# Module_RS485.net
KiCad netlist of a schematic drawn in Altium Designer
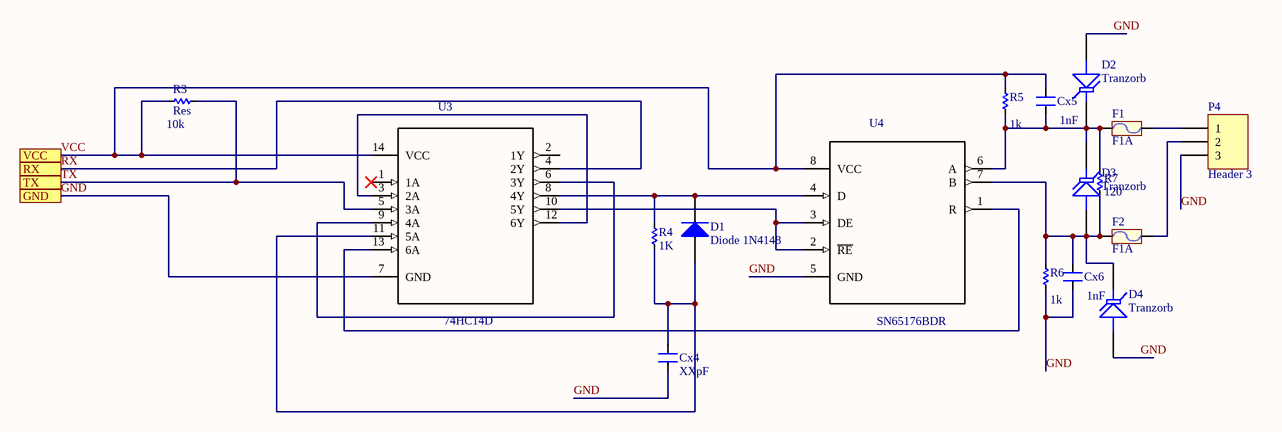
[diagram p0: Module RS485.SchDoc]

(export (version "E")
  (design (tool "Eeschema 10.0.6"))
  (components
    (comp (ref "Cx4")
      (value "XXpF")
      (footprint "CN-SMD-1206")
      (libsource (lib "LIBRARY_altium mulinhkien") (part "CN"))
    )
    (comp (ref "Cx5")
      (value "1nF")
      (footprint "CN-SMD-1206")
      (libsource (lib "LIBRARY_altium mulinhkien") (part "CN"))
    )
    (comp (ref "Cx6")
      (value "1nF")
      (footprint "CN-SMD-1206")
      (libsource (lib "LIBRARY_altium mulinhkien") (part "CN"))
    )
    (comp (ref "D1")
      (value "Diode 1N4148")
      (footprint "DO-35")
      (description "High Conductance Fast Diode")
      (fields (field (name "PUBLISHER") "Altium Limited"))
      (libsource (lib "Miscellaneous Devices") (part "Diode 1N4148"))
    )
    (comp (ref "D2")
      (value "Tranzorb")
      (footprint "DO-7")
      (description "Transient Voltage Suppression (TVS) Diode")
      (fields (field (name "PUBLISHER") "Altium Limited"))
      (libsource (lib "Miscellaneous Devices") (part "Tranzorb"))
    )
    (comp (ref "D3")
      (value "Tranzorb")
      (footprint "DO-7")
      (description "Transient Voltage Suppression (TVS) Diode")
      (fields (field (name "PUBLISHER") "Altium Limited"))
      (libsource (lib "Miscellaneous Devices") (part "Tranzorb"))
    )
    (comp (ref "D4")
      (value "Tranzorb")
      (footprint "DO-7")
      (description "Transient Voltage Suppression (TVS) Diode")
      (fields (field (name "PUBLISHER") "Altium Limited"))
      (libsource (lib "Miscellaneous Devices") (part "Tranzorb"))
    )
    (comp (ref "F1")
      (value "F1A")
      (footprint "Fuse3")
      (description "Fuse")
      (fields (field (name "DESIGNED BY") "VanDungEvn"))
      (libsource (lib "LIBRARY_altium mulinhkien") (part "Fuse"))
    )
    (comp (ref "F2")
      (value "F1A")
      (footprint "Fuse3")
      (description "Fuse")
      (fields (field (name "DESIGNED BY") "VanDungEvn"))
      (libsource (lib "LIBRARY_altium mulinhkien") (part "Fuse"))
    )
    (comp (ref "P4")
      (value "Header 3")
      (footprint "HDR1X3")
      (description "Header, 3-Pin")
      (fields (field (name "PUBLISHER") "Altium Limited"))
      (libsource (lib "Miscellaneous Connectors") (part "Header 3"))
    )
    (comp (ref "R3")
      (value "Res")
      (footprint "RES-SMD-1206")
      (description "Resistor")
      (fields
        (field (name "MANUFACTURER") "Generic Components")
        (field (name "ALTIUM_VALUE") "10k")
        (field (name "PUBLISHER") "Altium Hobart Technology Centre")
      )
      (libsource (lib "LIBRARY_altium mulinhkien") (part "Res-SMD"))
    )
    (comp (ref "R4")
      (value "1K")
      (footprint "RES-SMD-1206")
      (description "Resistor")
      (fields
        (field (name "MANUFACTURER") "Generic Components")
        (field (name "PUBLISHER") "Altium Hobart Technology Centre")
      )
      (libsource (lib "LIBRARY_altium mulinhkien") (part "Res-SMD"))
    )
    (comp (ref "R5")
      (value "1k")
      (footprint "RES-SMD-1206")
      (description "Resistor")
      (fields
        (field (name "MANUFACTURER") "Generic Components")
        (field (name "PUBLISHER") "Altium Hobart Technology Centre")
      )
      (libsource (lib "LIBRARY_altium mulinhkien") (part "Res-SMD"))
    )
    (comp (ref "R6")
      (value "1k")
      (footprint "RES-SMD-1206")
      (description "Resistor")
      (fields
        (field (name "MANUFACTURER") "Generic Components")
        (field (name "PUBLISHER") "Altium Hobart Technology Centre")
      )
      (libsource (lib "LIBRARY_altium mulinhkien") (part "Res-SMD"))
    )
    (comp (ref "R7")
      (value "120")
      (footprint "RES-SMD-1206")
      (description "Resistor")
      (fields
        (field (name "MANUFACTURER") "Generic Components")
        (field (name "PUBLISHER") "Altium Hobart Technology Centre")
      )
      (libsource (lib "LIBRARY_altium mulinhkien") (part "Res-SMD"))
    )
    (comp (ref "U3")
      (value "74HC14D")
      (footprint "*SOIC127P600X175-14N")
      (description "74HC CMOS logic IC series SOIC14 Hex Schmitt Inverter")
      (fields
        (field (name "DIGI-KEY_PART_NUMBER") "74HC14DCT-ND")
        (field (name "MF") "Toshiba Semiconductor")
      )
      (libsource (lib "74HC14D") (part "74HC14D"))
    )
    (comp (ref "U4")
      (value "SN65176BDR")
      (footprint "*SOIC127P600X175-8N")
      (description "Single Transmitter/Receiver RS-422/RS-485 8-Pin SOIC T/R")
      (fields (field (name "DIGI-KEY_PART_NUMBER") "296-14636-1-ND") (field (name "MF") "Texas Instruments"))
      (libsource (lib "SN65176BDR") (part "SN65176BDR"))
    )
  )
  (nets
    (net (code "1") (name "/GND") (class "Default")
      (node (ref "Cx4") (pin "1") (pinfunction "1_1") (pintype "passive"))
      (node (ref "Cx6") (pin "2") (pinfunction "2_2") (pintype "passive"))
      (node (ref "D2") (pin "1") (pinfunction "A_1") (pintype "passive"))
      (node (ref "D4") (pin "1") (pinfunction "A_1") (pintype "passive"))
      (node (ref "P4") (pin "3") (pinfunction "3_3") (pintype "passive"))
      (node (ref "R6") (pin "1") (pinfunction "1_1") (pintype "passive"))
      (node (ref "U3") (pin "7") (pinfunction "GND_7") (pintype "passive"))
      (node (ref "U4") (pin "5") (pinfunction "GND_5") (pintype "passive"))
    )
    (net (code "2") (name "/RX") (class "Default")
      (node (ref "U3") (pin "4") (pinfunction "2Y_4") (pintype "output"))
    )
    (net (code "3") (name "/TX") (class "Default")
      (node (ref "R3") (pin "2") (pinfunction "2_2") (pintype "passive"))
      (node (ref "U3") (pin "5") (pinfunction "3A_5") (pintype "input"))
    )
    (net (code "4") (name "/VCC") (class "Default")
      (node (ref "Cx5") (pin "1") (pinfunction "1_1") (pintype "passive"))
      (node (ref "R3") (pin "1") (pinfunction "1_1") (pintype "passive"))
      (node (ref "R5") (pin "2") (pinfunction "2_2") (pintype "passive"))
      (node (ref "U3") (pin "14") (pinfunction "VCC_14") (pintype "power_in"))
      (node (ref "U4") (pin "8") (pinfunction "VCC_8") (pintype "power_in"))
    )
    (net (code "5") (name "Net-(D1-A)") (class "Default")
      (node (ref "Cx4") (pin "2") (pinfunction "2_2") (pintype "passive"))
      (node (ref "D1") (pin "1") (pinfunction "A_1") (pintype "passive"))
      (node (ref "R4") (pin "2") (pinfunction "2_2") (pintype "passive"))
      (node (ref "U3") (pin "11") (pinfunction "5A_11") (pintype "input"))
    )
    (net (code "6") (name "Net-(D1-K)") (class "Default")
      (node (ref "D1") (pin "2") (pinfunction "K_2") (pintype "passive"))
      (node (ref "R4") (pin "1") (pinfunction "1_1") (pintype "passive"))
      (node (ref "U3") (pin "8") (pinfunction "4Y_8") (pintype "output"))
      (node (ref "U4") (pin "4") (pinfunction "D_4") (pintype "input"))
    )
    (net (code "7") (name "Net-(D2-K)") (class "Default")
      (node (ref "Cx5") (pin "2") (pinfunction "2_2") (pintype "passive"))
      (node (ref "D2") (pin "2") (pinfunction "K_2") (pintype "passive"))
      (node (ref "D3") (pin "2") (pinfunction "K_2") (pintype "passive"))
      (node (ref "F1") (pin "1") (pinfunction "1_1") (pintype "passive"))
      (node (ref "R5") (pin "1") (pinfunction "1_1") (pintype "passive"))
      (node (ref "R7") (pin "1") (pinfunction "1_1") (pintype "passive"))
      (node (ref "U4") (pin "6") (pinfunction "A_6") (pintype "output"))
    )
    (net (code "8") (name "Net-(D3-A)") (class "Default")
      (node (ref "Cx6") (pin "1") (pinfunction "1_1") (pintype "passive"))
      (node (ref "D3") (pin "1") (pinfunction "A_1") (pintype "passive"))
      (node (ref "D4") (pin "2") (pinfunction "K_2") (pintype "passive"))
      (node (ref "F2") (pin "1") (pinfunction "1_1") (pintype "passive"))
      (node (ref "R6") (pin "2") (pinfunction "2_2") (pintype "passive"))
      (node (ref "R7") (pin "2") (pinfunction "2_2") (pintype "passive"))
      (node (ref "U4") (pin "7") (pinfunction "B_7") (pintype "output"))
    )
    (net (code "9") (name "Net-(F1-Pad2)") (class "Default")
      (node (ref "F1") (pin "2") (pinfunction "2_2") (pintype "passive"))
      (node (ref "P4") (pin "1") (pinfunction "1_1") (pintype "passive"))
    )
    (net (code "10") (name "Net-(F2-Pad2)") (class "Default")
      (node (ref "F2") (pin "2") (pinfunction "2_2") (pintype "passive"))
      (node (ref "P4") (pin "2") (pinfunction "2_2") (pintype "passive"))
    )
    (net (code "11") (name "Net-(U3-2A)") (class "Default")
      (node (ref "U3") (pin "12") (pinfunction "6Y_12") (pintype "output"))
      (node (ref "U3") (pin "3") (pinfunction "2A_3") (pintype "input"))
    )
    (net (code "12") (name "Net-(U3-3Y)") (class "Default")
      (node (ref "U3") (pin "6") (pinfunction "3Y_6") (pintype "output"))
      (node (ref "U3") (pin "9") (pinfunction "4A_9") (pintype "input"))
    )
    (net (code "13") (name "Net-(U3-5Y)") (class "Default")
      (node (ref "U3") (pin "10") (pinfunction "5Y_10") (pintype "output"))
      (node (ref "U4") (pin "2") (pinfunction "~{RE}_2") (pintype "input"))
      (node (ref "U4") (pin "3") (pinfunction "DE_3") (pintype "input"))
    )
    (net (code "14") (name "Net-(U3-6A)") (class "Default")
      (node (ref "U3") (pin "13") (pinfunction "6A_13") (pintype "input"))
      (node (ref "U4") (pin "1") (pinfunction "R_1") (pintype "output"))
    )
    (net (code "15") (name "unconnected-(U3-1A-Pad1)") (class "Default")
      (node (ref "U3") (pin "1") (pinfunction "1A_1") (pintype "input+no_connect"))
    )
    (net (code "16") (name "unconnected-(U3-1Y-Pad2)") (class "Default")
      (node (ref "U3") (pin "2") (pinfunction "1Y_2") (pintype "output"))
    )
  )
)
